# Analogue_frontend.net
KiCad netlist of a schematic drawn in Altium Designer
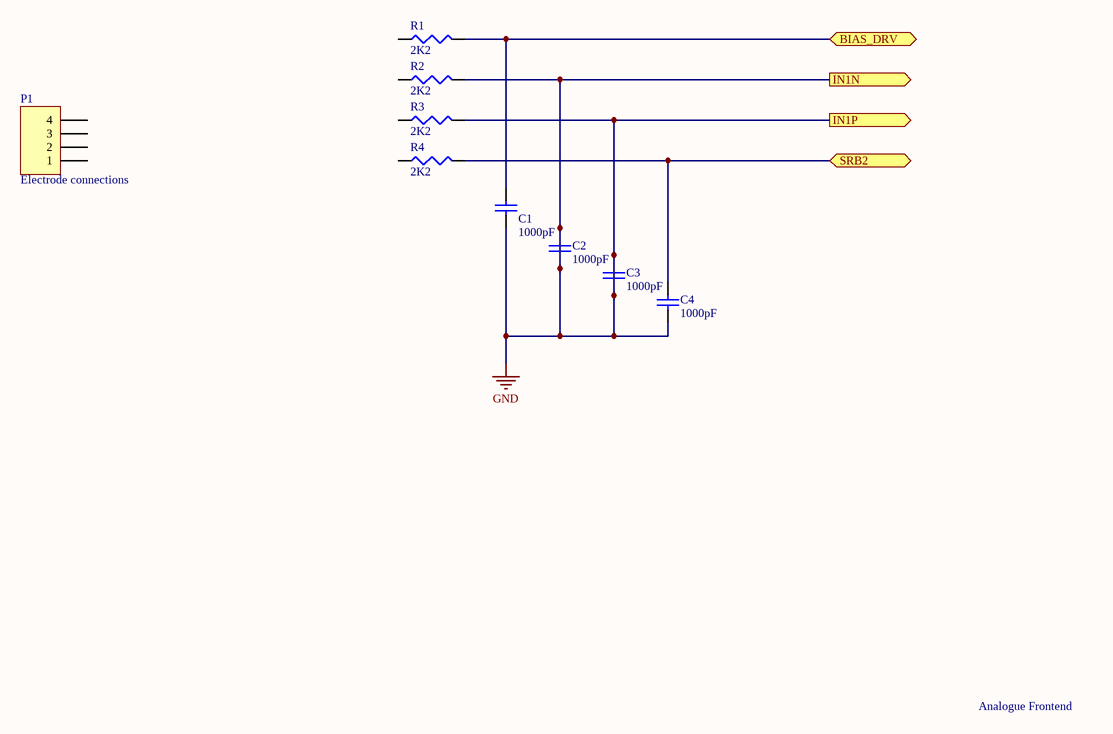
[diagram p0: Analogue_frontend.SchDoc]

(export (version "E")
  (design (tool "Eeschema 10.0.6"))
  (components
    (comp (ref "C1")
      (value "1000pF")
      (footprint "1608[0603]")
      (description "Capacitor (Semiconductor SIM Model)")
      (fields (field (name "Comment") "Cap Semi") (field (name "PUBLISHER") "Altium Limited"))
      (libsource (lib "Miscellaneous Devices") (part "Cap Semi"))
    )
    (comp (ref "C2")
      (value "1000pF")
      (footprint "1608[0603]")
      (description "Capacitor (Semiconductor SIM Model)")
      (fields (field (name "Comment") "Cap Semi") (field (name "PUBLISHER") "Altium Limited"))
      (libsource (lib "Miscellaneous Devices") (part "Cap Semi"))
    )
    (comp (ref "C3")
      (value "1000pF")
      (footprint "1608[0603]")
      (description "Capacitor (Semiconductor SIM Model)")
      (fields (field (name "Comment") "Cap Semi") (field (name "PUBLISHER") "Altium Limited"))
      (libsource (lib "Miscellaneous Devices") (part "Cap Semi"))
    )
    (comp (ref "C4")
      (value "1000pF")
      (footprint "1608[0603]")
      (description "Capacitor (Semiconductor SIM Model)")
      (fields (field (name "Comment") "Cap Semi") (field (name "PUBLISHER") "Altium Limited"))
      (libsource (lib "Miscellaneous Devices") (part "Cap Semi"))
    )
    (comp (ref "P1")
      (value "Electrode connections")
      (footprint "HDR1X4")
      (description "Header, 4-Pin")
      (fields (field (name "PUBLISHER") "Altium Limited"))
      (libsource (lib "Miscellaneous Connectors") (part "Header 4"))
    )
    (comp (ref "R1")
      (value "2K2")
      (footprint "J1-0603")
      (description "Resistor")
      (fields (field (name "Comment") "Res3") (field (name "PUBLISHER") "Altium Limited"))
      (libsource (lib "Miscellaneous Devices") (part "Res3"))
    )
    (comp (ref "R2")
      (value "2K2")
      (footprint "J1-0603")
      (description "Resistor")
      (fields (field (name "Comment") "Res3") (field (name "PUBLISHER") "Altium Limited"))
      (libsource (lib "Miscellaneous Devices") (part "Res3"))
    )
    (comp (ref "R3")
      (value "2K2")
      (footprint "J1-0603")
      (description "Resistor")
      (fields (field (name "Comment") "Res3") (field (name "PUBLISHER") "Altium Limited"))
      (libsource (lib "Miscellaneous Devices") (part "Res3"))
    )
    (comp (ref "R4")
      (value "2K2")
      (footprint "J1-0603")
      (description "Resistor")
      (fields (field (name "Comment") "Res3") (field (name "PUBLISHER") "Altium Limited"))
      (libsource (lib "Miscellaneous Devices") (part "Res3"))
    )
  )
  (nets
    (net (code "1") (name "/BIAS_DRV") (class "Default")
      (node (ref "C1") (pin "2") (pinfunction "2_2") (pintype "passive"))
      (node (ref "R1") (pin "2") (pinfunction "2_2") (pintype "passive"))
    )
    (net (code "2") (name "/SRB2") (class "Default")
      (node (ref "C4") (pin "2") (pinfunction "2_2") (pintype "passive"))
      (node (ref "R4") (pin "2") (pinfunction "2_2") (pintype "passive"))
    )
    (net (code "3") (name "GND") (class "Default")
      (node (ref "C1") (pin "1") (pinfunction "1_1") (pintype "passive"))
      (node (ref "C2") (pin "1") (pinfunction "1_1") (pintype "passive"))
      (node (ref "C2") (pin "2") (pinfunction "2_2") (pintype "passive"))
      (node (ref "C3") (pin "1") (pinfunction "1_1") (pintype "passive"))
      (node (ref "C3") (pin "2") (pinfunction "2_2") (pintype "passive"))
      (node (ref "C4") (pin "1") (pinfunction "1_1") (pintype "passive"))
      (node (ref "R2") (pin "2") (pinfunction "2_2") (pintype "passive"))
      (node (ref "R3") (pin "2") (pinfunction "2_2") (pintype "passive"))
    )
    (net (code "4") (name "unconnected-(P1-Pad1)") (class "Default")
      (node (ref "P1") (pin "1") (pinfunction "1_1") (pintype "passive"))
    )
    (net (code "5") (name "unconnected-(P1-Pad2)") (class "Default")
      (node (ref "P1") (pin "2") (pinfunction "2_2") (pintype "passive"))
    )
    (net (code "6") (name "unconnected-(P1-Pad3)") (class "Default")
      (node (ref "P1") (pin "3") (pinfunction "3_3") (pintype "passive"))
    )
    (net (code "7") (name "unconnected-(P1-Pad4)") (class "Default")
      (node (ref "P1") (pin "4") (pinfunction "4_4") (pintype "passive"))
    )
    (net (code "8") (name "unconnected-(R1-Pad1)") (class "Default")
      (node (ref "R1") (pin "1") (pinfunction "1_1") (pintype "passive"))
    )
    (net (code "9") (name "unconnected-(R2-Pad1)") (class "Default")
      (node (ref "R2") (pin "1") (pinfunction "1_1") (pintype "passive"))
    )
    (net (code "10") (name "unconnected-(R3-Pad1)") (class "Default")
      (node (ref "R3") (pin "1") (pinfunction "1_1") (pintype "passive"))
    )
    (net (code "11") (name "unconnected-(R4-Pad1)") (class "Default")
      (node (ref "R4") (pin "1") (pinfunction "1_1") (pintype "passive"))
    )
  )
)
